# amp_lm1876_ocl_v2.net
KiCad netlist of a schematic drawn in EAGLE
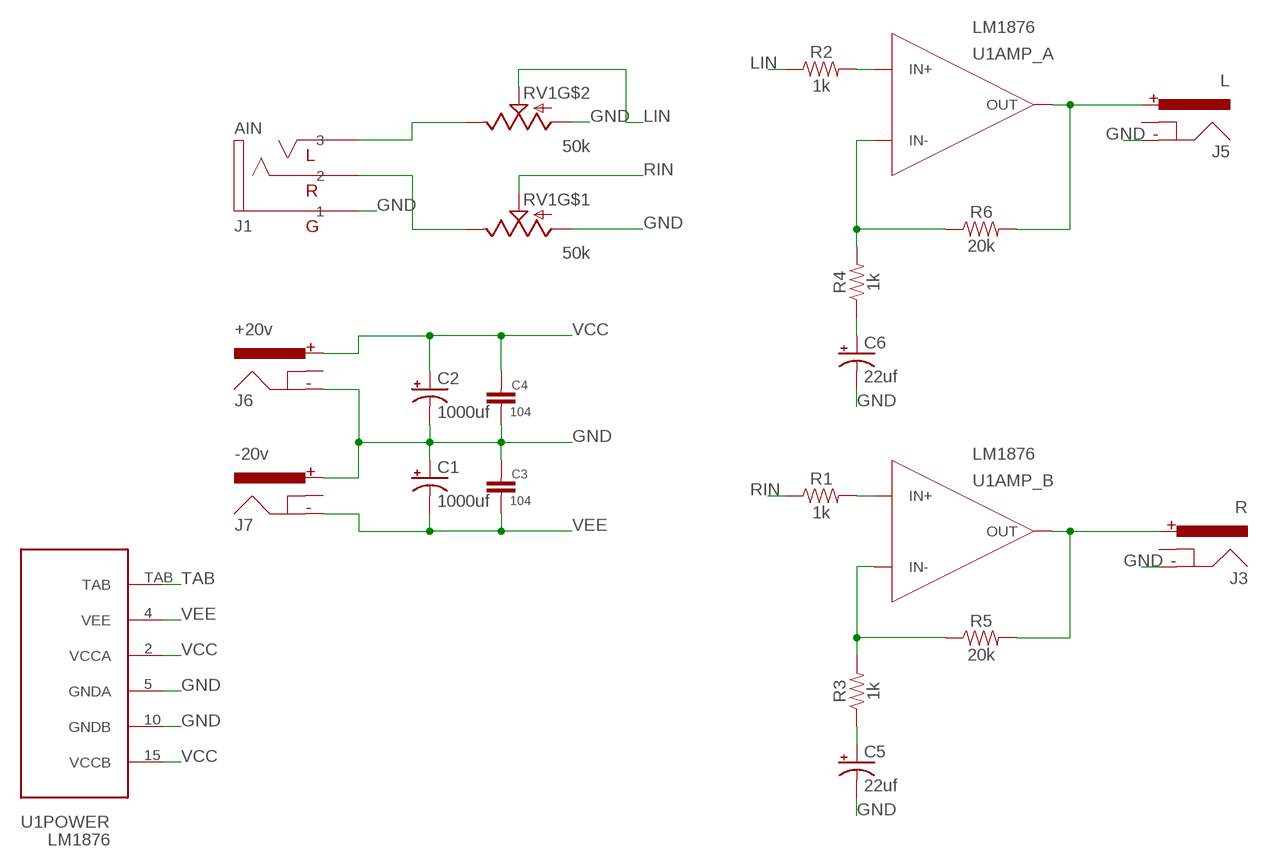
[diagram p0: schematic, sheet 1]

(export (version "E")
  (design (tool "Eeschema 10.0.6"))
  (components
    (comp (ref "C1")
      (value "1000uf")
      (footprint "eagle-import:CAP_5MM_10D")
      (libsource (lib "eagle-import") (part "CAP5MM"))
    )
    (comp (ref "C2")
      (value "1000uf")
      (footprint "eagle-import:CAP_5MM_10D")
      (libsource (lib "eagle-import") (part "CAP5MM"))
    )
    (comp (ref "C3")
      (value "104")
      (footprint "eagle-import:C0603")
      (libsource (lib "eagle-import") (part "CAP_SMDC0603"))
    )
    (comp (ref "C4")
      (value "104")
      (footprint "eagle-import:C0603")
      (libsource (lib "eagle-import") (part "CAP_SMDC0603"))
    )
    (comp (ref "C5")
      (value "22uf")
      (footprint "eagle-import:CAP_2.5MM")
      (libsource (lib "eagle-import") (part "CAP"))
    )
    (comp (ref "C6")
      (value "22uf")
      (footprint "eagle-import:CAP_2.5MM")
      (libsource (lib "eagle-import") (part "CAP"))
    )
    (comp (ref "J1")
      (value "AIN")
      (footprint "eagle-import:3.5MM")
      (libsource (lib "eagle-import") (part "3.5MM_PHONE"))
    )
    (comp (ref "J3")
      (value "R")
      (footprint "eagle-import:POWER_JACK_PTH_LOCK")
      (libsource (lib "eagle-import") (part "POWER_JACKPTH_LOCK"))
    )
    (comp (ref "J5")
      (value "L")
      (footprint "eagle-import:POWER_JACK_PTH_LOCK")
      (libsource (lib "eagle-import") (part "POWER_JACKPTH_LOCK"))
    )
    (comp (ref "J6")
      (value "+20v")
      (footprint "eagle-import:POWER_JACK_PTH_LOCK")
      (libsource (lib "eagle-import") (part "POWER_JACKPTH_LOCK"))
    )
    (comp (ref "J7")
      (value "-20v")
      (footprint "eagle-import:POWER_JACK_PTH_LOCK")
      (libsource (lib "eagle-import") (part "POWER_JACKPTH_LOCK"))
    )
    (comp (ref "R1")
      (value "1k")
      (footprint "eagle-import:R0603")
      (libsource (lib "eagle-import") (part "RESISTOR_SMDR0603"))
    )
    (comp (ref "R2")
      (value "1k")
      (footprint "eagle-import:R0603")
      (libsource (lib "eagle-import") (part "RESISTOR_SMDR0603"))
    )
    (comp (ref "R3")
      (value "1k")
      (footprint "eagle-import:R0603")
      (libsource (lib "eagle-import") (part "RESISTOR_SMDR0603"))
    )
    (comp (ref "R4")
      (value "1k")
      (footprint "eagle-import:R0603")
      (libsource (lib "eagle-import") (part "RESISTOR_SMDR0603"))
    )
    (comp (ref "R5")
      (value "20k")
      (footprint "eagle-import:R0603")
      (libsource (lib "eagle-import") (part "RESISTOR_SMDR0603"))
    )
    (comp (ref "R6")
      (value "20k")
      (footprint "eagle-import:R0603")
      (libsource (lib "eagle-import") (part "RESISTOR_SMDR0603"))
    )
    (comp (ref "RV1")
      (value "50k")
      (footprint "eagle-import:POT_DUAL_GREEN")
      (libsource (lib "eagle-import") (part "POT_DUALPOT_DUAL_GREEN"))
    )
    (comp (ref "U1")
      (value "LM1876")
      (footprint "eagle-import:MULTIWATT15_FLAT")
      (libsource (lib "eagle-import") (part "LM1876MULTIWATT15"))
    )
  )
  (nets
    (net (code "1") (name "/GND") (class "Default")
      (node (ref "C1") (pin "+") (pinfunction "+_+") (pintype "passive"))
      (node (ref "C2") (pin "-") (pinfunction "-_-") (pintype "passive"))
      (node (ref "C3") (pin "1") (pinfunction "1_1") (pintype "passive"))
      (node (ref "C4") (pin "2") (pinfunction "2_2") (pintype "passive"))
      (node (ref "C5") (pin "-") (pinfunction "-_-") (pintype "passive"))
      (node (ref "C6") (pin "-") (pinfunction "-_-") (pintype "passive"))
      (node (ref "J1") (pin "P$1") (pinfunction "1_P$1") (pintype "bidirectional"))
      (node (ref "J3") (pin "GND") (pinfunction "GND_GND") (pintype "bidirectional"))
      (node (ref "J5") (pin "GND") (pinfunction "GND_GND") (pintype "bidirectional"))
      (node (ref "J6") (pin "GND") (pinfunction "GND_GND") (pintype "bidirectional"))
      (node (ref "J7") (pin "PWR") (pinfunction "PWR_PWR") (pintype "bidirectional"))
      (node (ref "RV1") (pin "P$1") (pinfunction "A_P$1") (pintype "passive"))
      (node (ref "RV1") (pin "P$4") (pinfunction "A_P$4") (pintype "passive"))
      (node (ref "U1") (pin "10") (pinfunction "GNDB_10") (pintype "bidirectional"))
      (node (ref "U1") (pin "5") (pinfunction "GNDA_5") (pintype "bidirectional"))
    )
    (net (code "2") (name "/LIN") (class "Default")
      (node (ref "R2") (pin "1") (pinfunction "1_1") (pintype "passive"))
      (node (ref "RV1") (pin "P$5") (pinfunction "S_P$5") (pintype "passive"))
    )
    (net (code "3") (name "/RIN") (class "Default")
      (node (ref "R1") (pin "1") (pinfunction "1_1") (pintype "passive"))
      (node (ref "RV1") (pin "P$2") (pinfunction "S_P$2") (pintype "passive"))
    )
    (net (code "4") (name "/TAB") (class "Default")
      (node (ref "U1") (pin "TAB") (pinfunction "TAB_TAB") (pintype "bidirectional"))
    )
    (net (code "5") (name "/VCC") (class "Default")
      (node (ref "C2") (pin "+") (pinfunction "+_+") (pintype "passive"))
      (node (ref "C4") (pin "1") (pinfunction "1_1") (pintype "passive"))
      (node (ref "J6") (pin "PWR") (pinfunction "PWR_PWR") (pintype "bidirectional"))
      (node (ref "U1") (pin "15") (pinfunction "VCCB_15") (pintype "bidirectional"))
      (node (ref "U1") (pin "2") (pinfunction "VCCA_2") (pintype "bidirectional"))
    )
    (net (code "6") (name "/VEE") (class "Default")
      (node (ref "C1") (pin "-") (pinfunction "-_-") (pintype "passive"))
      (node (ref "C3") (pin "2") (pinfunction "2_2") (pintype "passive"))
      (node (ref "J7") (pin "GND") (pinfunction "GND_GND") (pintype "bidirectional"))
      (node (ref "U1") (pin "4") (pinfunction "VEE_4") (pintype "bidirectional"))
    )
    (net (code "7") (name "Net-(C5-Pad+)") (class "Default")
      (node (ref "C5") (pin "+") (pinfunction "+_+") (pintype "passive"))
      (node (ref "R3") (pin "1") (pinfunction "1_1") (pintype "passive"))
    )
    (net (code "8") (name "Net-(C6-Pad+)") (class "Default")
      (node (ref "C6") (pin "+") (pinfunction "+_+") (pintype "passive"))
      (node (ref "R4") (pin "1") (pinfunction "1_1") (pintype "passive"))
    )
    (net (code "9") (name "Net-(J1-2)") (class "Default")
      (node (ref "J1") (pin "P$2") (pinfunction "2_P$2") (pintype "bidirectional"))
      (node (ref "RV1") (pin "P$3") (pinfunction "E_P$3") (pintype "passive"))
    )
    (net (code "10") (name "Net-(J1-3)") (class "Default")
      (node (ref "J1") (pin "P$3") (pinfunction "3_P$3") (pintype "bidirectional"))
      (node (ref "RV1") (pin "P$6") (pinfunction "E_P$6") (pintype "passive"))
    )
    (net (code "11") (name "Net-(U1A-IN+)") (class "Default")
      (node (ref "R2") (pin "2") (pinfunction "2_2") (pintype "passive"))
      (node (ref "U1") (pin "8") (pinfunction "IN+_8") (pintype "bidirectional"))
    )
    (net (code "12") (name "Net-(U1A-IN-)") (class "Default")
      (node (ref "R4") (pin "2") (pinfunction "2_2") (pintype "passive"))
      (node (ref "R6") (pin "1") (pinfunction "1_1") (pintype "passive"))
      (node (ref "U1") (pin "7") (pinfunction "IN-_7") (pintype "bidirectional"))
    )
    (net (code "13") (name "Net-(U1A-OUT)") (class "Default")
      (node (ref "J5") (pin "PWR") (pinfunction "PWR_PWR") (pintype "bidirectional"))
      (node (ref "R6") (pin "2") (pinfunction "2_2") (pintype "passive"))
      (node (ref "U1") (pin "3") (pinfunction "OUT_3") (pintype "bidirectional"))
    )
    (net (code "14") (name "Net-(U1B-IN+)") (class "Default")
      (node (ref "R1") (pin "2") (pinfunction "2_2") (pintype "passive"))
      (node (ref "U1") (pin "13") (pinfunction "IN+_13") (pintype "bidirectional"))
    )
    (net (code "15") (name "Net-(U1B-IN-)") (class "Default")
      (node (ref "R3") (pin "2") (pinfunction "2_2") (pintype "passive"))
      (node (ref "R5") (pin "1") (pinfunction "1_1") (pintype "passive"))
      (node (ref "U1") (pin "12") (pinfunction "IN-_12") (pintype "bidirectional"))
    )
    (net (code "16") (name "Net-(U1B-OUT)") (class "Default")
      (node (ref "J3") (pin "PWR") (pinfunction "PWR_PWR") (pintype "bidirectional"))
      (node (ref "R5") (pin "2") (pinfunction "2_2") (pintype "passive"))
      (node (ref "U1") (pin "1") (pinfunction "OUT_1") (pintype "bidirectional"))
    )
    (net (code "17") (name "unconnected-(J3-PadGNDBREAK)") (class "Default")
      (node (ref "J3") (pin "GNDBREAK") (pinfunction "GNDBREAK_GNDBREAK") (pintype "bidirectional"))
    )
    (net (code "18") (name "unconnected-(J5-PadGNDBREAK)") (class "Default")
      (node (ref "J5") (pin "GNDBREAK") (pinfunction "GNDBREAK_GNDBREAK") (pintype "bidirectional"))
    )
    (net (code "19") (name "unconnected-(J6-PadGNDBREAK)") (class "Default")
      (node (ref "J6") (pin "GNDBREAK") (pinfunction "GNDBREAK_GNDBREAK") (pintype "bidirectional"))
    )
    (net (code "20") (name "unconnected-(J7-PadGNDBREAK)") (class "Default")
      (node (ref "J7") (pin "GNDBREAK") (pinfunction "GNDBREAK_GNDBREAK") (pintype "bidirectional"))
    )
  )
)
